# MCU2.net
KiCad netlist of a schematic drawn in Altium Designer
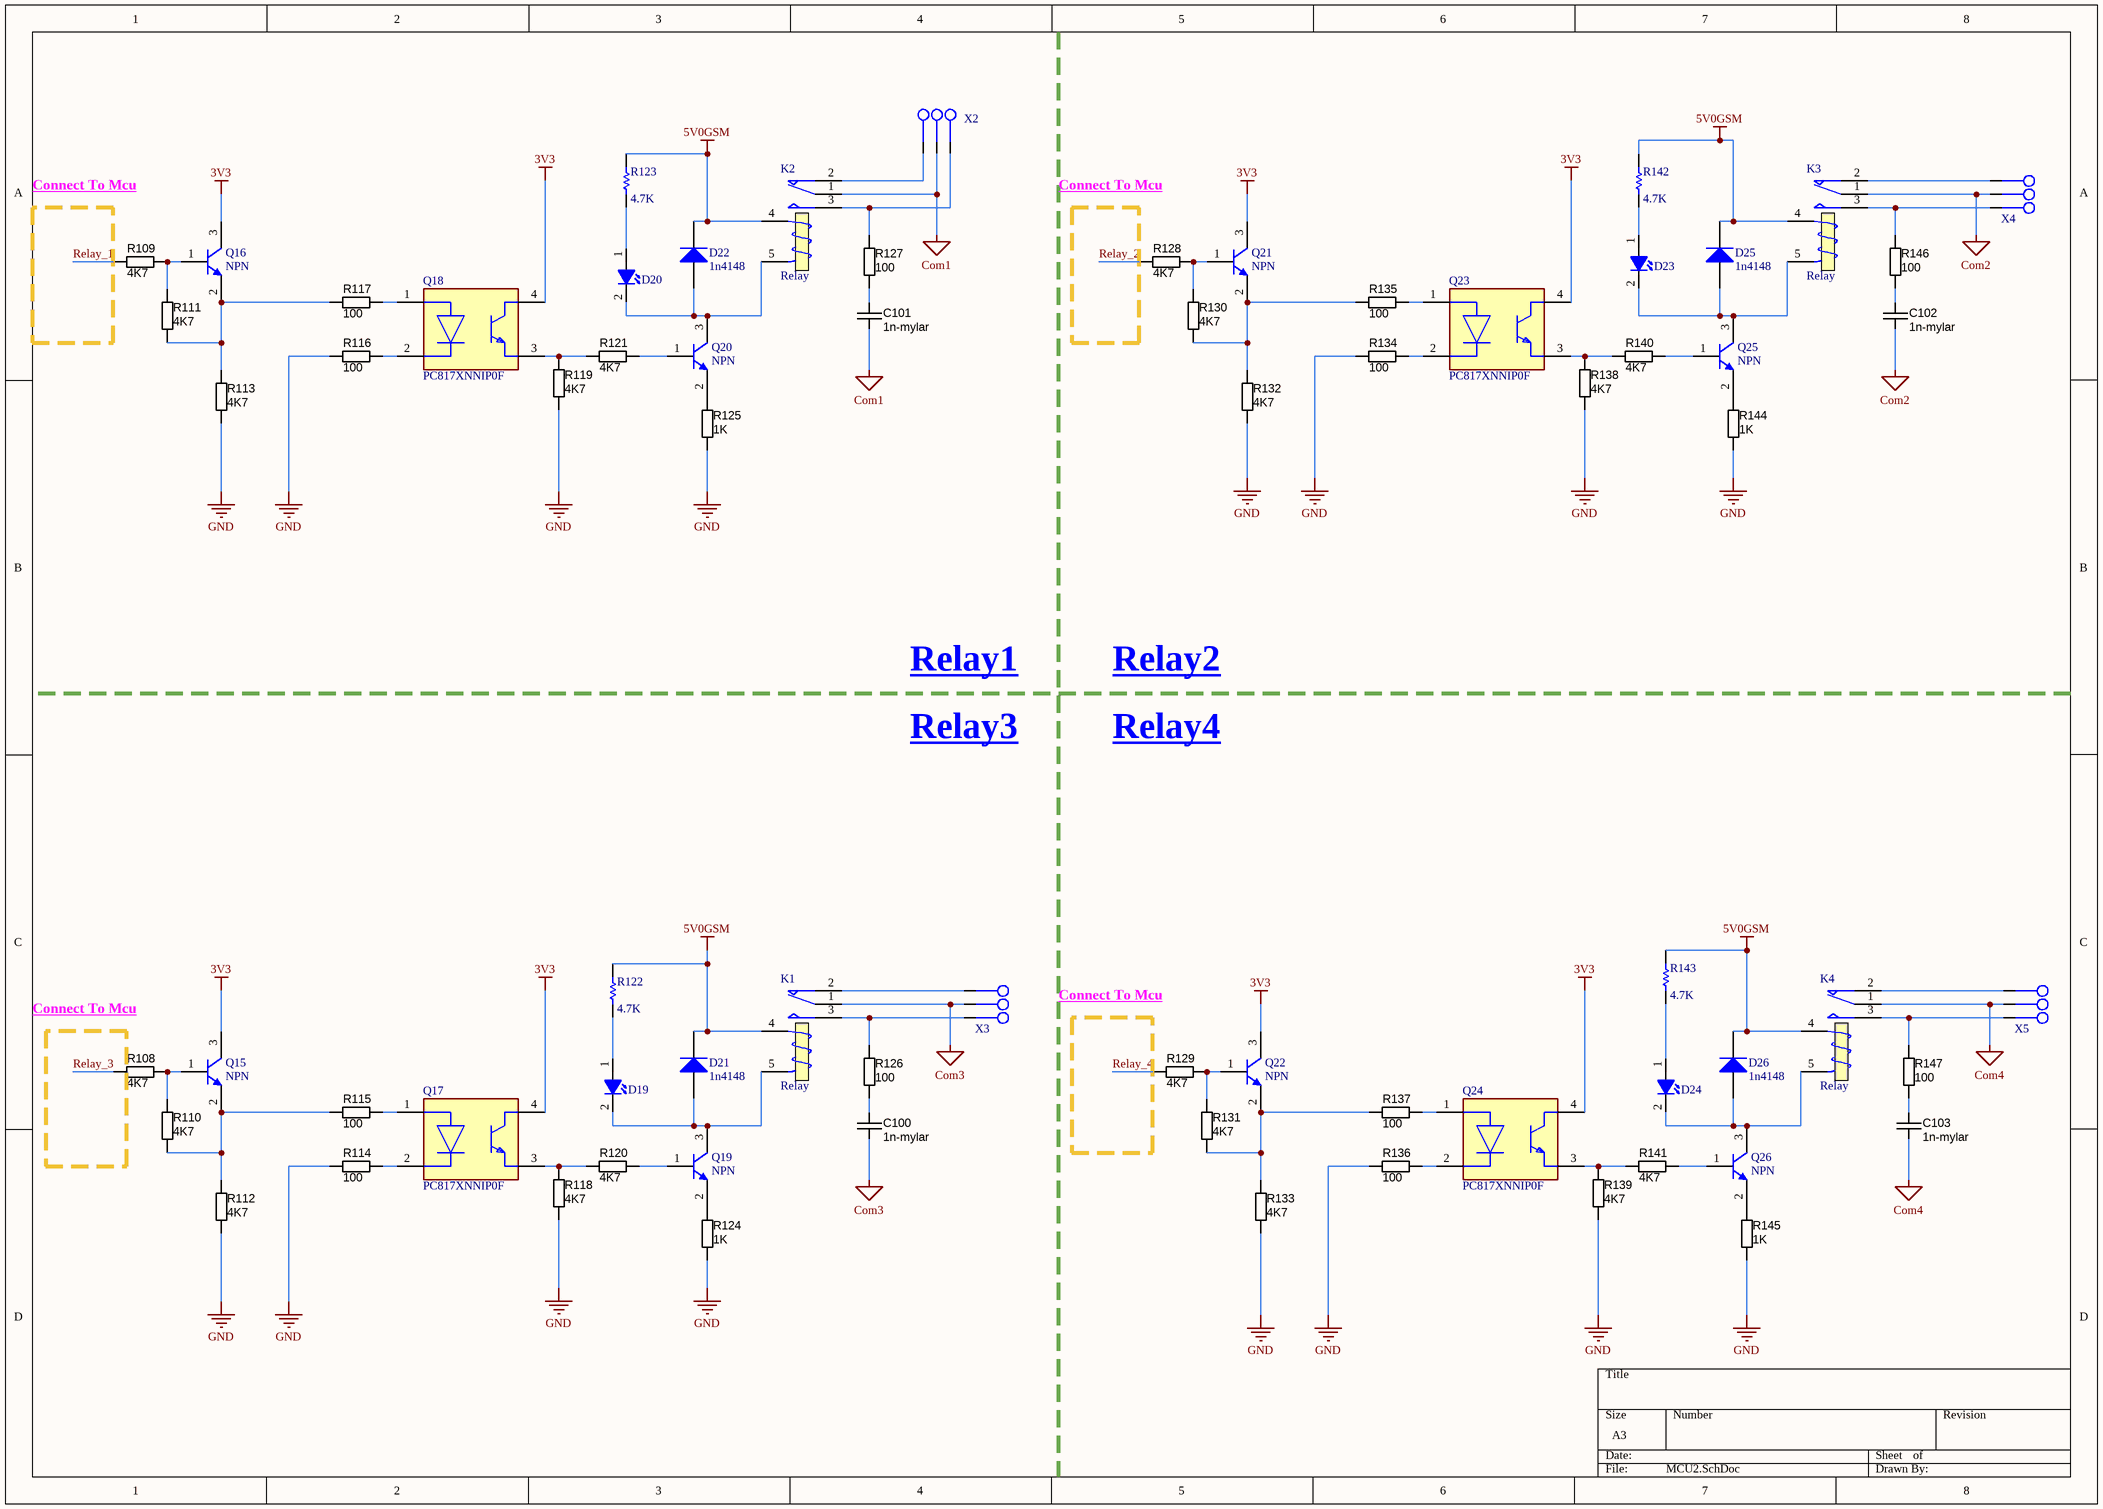
[diagram p0: MCU2.SchDoc]

(export (version "E")
  (design (tool "Eeschema 10.0.6"))
  (components
    (comp (ref "C100")
      (value "1n-mylar")
      (footprint "C_PLY_13X5")
      (description "Capacitor SMD Cer 1nF 10% 50V X7R 0603")
      (fields (field (name "TOLERANCE") "±10%") (field (name "Comment") "approved sub OK"))
      (libsource (lib "PBL - Capacitors") (part "CAPC_100n_0603_X7R_50V_10%"))
    )
    (comp (ref "C101")
      (value "1n-mylar")
      (footprint "C_PLY_13X5")
      (description "Capacitor SMD Cer 1nF 10% 50V X7R 0603")
      (fields (field (name "TOLERANCE") "±10%") (field (name "Comment") "approved sub OK"))
      (libsource (lib "PBL - Capacitors") (part "CAPC_100n_0603_X7R_50V_10%"))
    )
    (comp (ref "C102")
      (value "1n-mylar")
      (footprint "C_PLY_13X5")
      (description "Capacitor SMD Cer 1nF 10% 50V X7R 0603")
      (fields (field (name "TOLERANCE") "±10%") (field (name "Comment") "approved sub OK"))
      (libsource (lib "PBL - Capacitors") (part "CAPC_100n_0603_X7R_50V_10%"))
    )
    (comp (ref "C103")
      (value "1n-mylar")
      (footprint "C_PLY_13X5")
      (description "Capacitor SMD Cer 1nF 10% 50V X7R 0603")
      (fields (field (name "TOLERANCE") "±10%") (field (name "Comment") "approved sub OK"))
      (libsource (lib "PBL - Capacitors") (part "CAPC_100n_0603_X7R_50V_10%"))
    )
    (comp (ref "D19")
      (value "LED THD 5mm")
      (footprint "LED5MM_RED")
      (libsource (lib "LED") (part "LED THD 5mm"))
    )
    (comp (ref "D20")
      (value "LED THD 5mm")
      (footprint "LED5MM_RED")
      (libsource (lib "LED") (part "LED THD 5mm"))
    )
    (comp (ref "D21")
      (value "1n4148")
      (footprint "d_sod80")
      (description "Default Diode")
      (fields (field (name "PUBLISHER") "Altium Limited"))
      (libsource (lib "Miscellaneous Devices") (part "Diode"))
    )
    (comp (ref "D22")
      (value "1n4148")
      (footprint "d_sod80")
      (description "Default Diode")
      (fields (field (name "PUBLISHER") "Altium Limited"))
      (libsource (lib "Miscellaneous Devices") (part "Diode"))
    )
    (comp (ref "D23")
      (value "LED THD 5mm")
      (footprint "LED5MM_RED")
      (libsource (lib "LED") (part "LED THD 5mm"))
    )
    (comp (ref "D24")
      (value "LED THD 5mm")
      (footprint "LED5MM_RED")
      (libsource (lib "LED") (part "LED THD 5mm"))
    )
    (comp (ref "D25")
      (value "1n4148")
      (footprint "d_sod80")
      (description "Default Diode")
      (fields (field (name "PUBLISHER") "Altium Limited"))
      (libsource (lib "Miscellaneous Devices") (part "Diode"))
    )
    (comp (ref "D26")
      (value "1n4148")
      (footprint "d_sod80")
      (description "Default Diode")
      (fields (field (name "PUBLISHER") "Altium Limited"))
      (libsource (lib "Miscellaneous Devices") (part "Diode"))
    )
    (comp (ref "K1")
      (value "Relay")
      (footprint "REL_SPDT_5_2216")
      (description "SPDT Relay")
      (fields (field (name "PUBLISHER") "Altium Limited"))
      (libsource (lib "Miscellaneous Devices") (part "Relay"))
    )
    (comp (ref "K2")
      (value "Relay")
      (footprint "REL_SPDT_5_2216")
      (description "SPDT Relay")
      (fields (field (name "PUBLISHER") "Altium Limited"))
      (libsource (lib "Miscellaneous Devices") (part "Relay"))
    )
    (comp (ref "K3")
      (value "Relay")
      (footprint "REL_SPDT_5_2216")
      (description "SPDT Relay")
      (fields (field (name "PUBLISHER") "Altium Limited"))
      (libsource (lib "Miscellaneous Devices") (part "Relay"))
    )
    (comp (ref "K4")
      (value "Relay")
      (footprint "REL_SPDT_5_2216")
      (description "SPDT Relay")
      (fields (field (name "PUBLISHER") "Altium Limited"))
      (libsource (lib "Miscellaneous Devices") (part "Relay"))
    )
    (comp (ref "Q15")
      (value "NPN")
      (footprint "SOT23-3")
      (description "NPN Bipolar Transistor")
      (fields (field (name "PUBLISHER") "Altium Limited"))
      (libsource (lib "Miscellaneous Devices") (part "NPN"))
    )
    (comp (ref "Q16")
      (value "NPN")
      (footprint "SOT23-3")
      (description "NPN Bipolar Transistor")
      (fields (field (name "PUBLISHER") "Altium Limited"))
      (libsource (lib "Miscellaneous Devices") (part "NPN"))
    )
    (comp (ref "Q17")
      (value "PC817XNNIP0F")
      (footprint "FP-PC817XNNIP0F-MFG")
      (description "OPTOISOLATOR 5KV TRANS 4SMD")
      (libsource (lib "Altium Content Vault") (part "6470904bf6395c62928ee73e60120b8"))
    )
    (comp (ref "Q18")
      (value "PC817XNNIP0F")
      (footprint "FP-PC817XNNIP0F-MFG")
      (description "OPTOISOLATOR 5KV TRANS 4SMD")
      (libsource (lib "Altium Content Vault") (part "6470904bf6395c62928ee73e60120b8"))
    )
    (comp (ref "Q19")
      (value "NPN")
      (footprint "SOT23-3")
      (description "NPN Bipolar Transistor")
      (fields (field (name "PUBLISHER") "Altium Limited"))
      (libsource (lib "Miscellaneous Devices") (part "NPN"))
    )
    (comp (ref "Q20")
      (value "NPN")
      (footprint "SOT23-3")
      (description "NPN Bipolar Transistor")
      (fields (field (name "PUBLISHER") "Altium Limited"))
      (libsource (lib "Miscellaneous Devices") (part "NPN"))
    )
    (comp (ref "Q21")
      (value "NPN")
      (footprint "SOT23-3")
      (description "NPN Bipolar Transistor")
      (fields (field (name "PUBLISHER") "Altium Limited"))
      (libsource (lib "Miscellaneous Devices") (part "NPN"))
    )
    (comp (ref "Q22")
      (value "NPN")
      (footprint "SOT23-3")
      (description "NPN Bipolar Transistor")
      (fields (field (name "PUBLISHER") "Altium Limited"))
      (libsource (lib "Miscellaneous Devices") (part "NPN"))
    )
    (comp (ref "Q23")
      (value "PC817XNNIP0F")
      (footprint "FP-PC817XNNIP0F-MFG")
      (description "OPTOISOLATOR 5KV TRANS 4SMD")
      (libsource (lib "Altium Content Vault") (part "6470904bf6395c62928ee73e60120b8"))
    )
    (comp (ref "Q24")
      (value "PC817XNNIP0F")
      (footprint "FP-PC817XNNIP0F-MFG")
      (description "OPTOISOLATOR 5KV TRANS 4SMD")
      (libsource (lib "Altium Content Vault") (part "6470904bf6395c62928ee73e60120b8"))
    )
    (comp (ref "Q25")
      (value "NPN")
      (footprint "SOT23-3")
      (description "NPN Bipolar Transistor")
      (fields (field (name "PUBLISHER") "Altium Limited"))
      (libsource (lib "Miscellaneous Devices") (part "NPN"))
    )
    (comp (ref "Q26")
      (value "NPN")
      (footprint "SOT23-3")
      (description "NPN Bipolar Transistor")
      (fields (field (name "PUBLISHER") "Altium Limited"))
      (libsource (lib "Miscellaneous Devices") (part "NPN"))
    )
    (comp (ref "R108")
      (value "4K7")
      (footprint "RESC1608X55N")
      (description "Resistor SMD chip 4.7k Ohm 0.1W 5% 0603")
      (fields (field (name "TOLERANCE") "±5%") (field (name "Comment") "Thick Film"))
      (libsource (lib "") (part "RES_4K7_0603_5%_1"))
    )
    (comp (ref "R109")
      (value "4K7")
      (footprint "RESC1608X55N")
      (description "Resistor SMD chip 4.7k Ohm 0.1W 5% 0603")
      (fields (field (name "TOLERANCE") "±5%") (field (name "Comment") "Thick Film"))
      (libsource (lib "") (part "RES_4K7_0603_5%_1"))
    )
    (comp (ref "R110")
      (value "4K7")
      (footprint "RESC1608X55N")
      (description "Resistor SMD chip 4.7k Ohm 0.1W 5% 0603")
      (fields (field (name "TOLERANCE") "±5%") (field (name "Comment") "Thick Film"))
      (libsource (lib "PBL - Resistors") (part "RES_4K7_0603_5%"))
    )
    (comp (ref "R111")
      (value "4K7")
      (footprint "RESC1608X55N")
      (description "Resistor SMD chip 4.7k Ohm 0.1W 5% 0603")
      (fields (field (name "TOLERANCE") "±5%") (field (name "Comment") "Thick Film"))
      (libsource (lib "PBL - Resistors") (part "RES_4K7_0603_5%"))
    )
    (comp (ref "R112")
      (value "4K7")
      (footprint "RESC1608X55N")
      (description "Resistor SMD chip 4.7k Ohm 0.1W 5% 0603")
      (fields (field (name "TOLERANCE") "±5%") (field (name "Comment") "Thick Film"))
      (libsource (lib "PBL - Resistors") (part "RES_4K7_0603_5%"))
    )
    (comp (ref "R113")
      (value "4K7")
      (footprint "RESC1608X55N")
      (description "Resistor SMD chip 4.7k Ohm 0.1W 5% 0603")
      (fields (field (name "TOLERANCE") "±5%") (field (name "Comment") "Thick Film"))
      (libsource (lib "PBL - Resistors") (part "RES_4K7_0603_5%"))
    )
    (comp (ref "R114")
      (value "100")
      (footprint "RESC1608X55N")
      (description "Resistor SMD chip 100 Ohm 0.1W 5% 0603")
      (fields (field (name "TOLERANCE") "±5%") (field (name "Comment") "Thick Film"))
      (libsource (lib "") (part "RES_4K7_0603_5%_1"))
    )
    (comp (ref "R115")
      (value "100")
      (footprint "RESC1608X55N")
      (description "Resistor SMD chip 100 Ohm 0.1W 5% 0603")
      (fields (field (name "TOLERANCE") "±5%") (field (name "Comment") "Thick Film"))
      (libsource (lib "") (part "RES_4K7_0603_5%_1"))
    )
    (comp (ref "R116")
      (value "100")
      (footprint "RESC1608X55N")
      (description "Resistor SMD chip 100 Ohm 0.1W 5% 0603")
      (fields (field (name "TOLERANCE") "±5%") (field (name "Comment") "Thick Film"))
      (libsource (lib "") (part "RES_4K7_0603_5%_1"))
    )
    (comp (ref "R117")
      (value "100")
      (footprint "RESC1608X55N")
      (description "Resistor SMD chip 100 Ohm 0.1W 5% 0603")
      (fields (field (name "TOLERANCE") "±5%") (field (name "Comment") "Thick Film"))
      (libsource (lib "") (part "RES_4K7_0603_5%_1"))
    )
    (comp (ref "R118")
      (value "4K7")
      (footprint "RESC1608X55N")
      (description "Resistor SMD chip 4.7k Ohm 0.1W 5% 0603")
      (fields (field (name "TOLERANCE") "±5%") (field (name "Comment") "Thick Film"))
      (libsource (lib "PBL - Resistors") (part "RES_4K7_0603_5%"))
    )
    (comp (ref "R119")
      (value "4K7")
      (footprint "RESC1608X55N")
      (description "Resistor SMD chip 4.7k Ohm 0.1W 5% 0603")
      (fields (field (name "TOLERANCE") "±5%") (field (name "Comment") "Thick Film"))
      (libsource (lib "PBL - Resistors") (part "RES_4K7_0603_5%"))
    )
    (comp (ref "R120")
      (value "4K7")
      (footprint "RESC1608X55N")
      (description "Resistor SMD chip 4.7k Ohm 0.1W 5% 0603")
      (fields (field (name "TOLERANCE") "±5%") (field (name "Comment") "Thick Film"))
      (libsource (lib "") (part "RES_4K7_0603_5%_1"))
    )
    (comp (ref "R121")
      (value "4K7")
      (footprint "RESC1608X55N")
      (description "Resistor SMD chip 4.7k Ohm 0.1W 5% 0603")
      (fields (field (name "TOLERANCE") "±5%") (field (name "Comment") "Thick Film"))
      (libsource (lib "") (part "RES_4K7_0603_5%_1"))
    )
    (comp (ref "R122")
      (value "4.7K")
      (footprint "0603")
      (description "Resistor")
      (fields (field (name "Comment") "Res1") (field (name "PUBLISHER") "Altium Limited"))
      (libsource (lib "Miscellaneous Devices") (part "Res1"))
    )
    (comp (ref "R123")
      (value "4.7K")
      (footprint "0603")
      (description "Resistor")
      (fields (field (name "Comment") "Res1") (field (name "PUBLISHER") "Altium Limited"))
      (libsource (lib "Miscellaneous Devices") (part "Res1"))
    )
    (comp (ref "R124")
      (value "1K")
      (footprint "RESC1608X55N")
      (description "Resistor SMD chip 4.7k Ohm 0.1W 5% 0603")
      (fields (field (name "TOLERANCE") "±5%") (field (name "Comment") "Thick Film"))
      (libsource (lib "") (part "RES_4K7_0603_5%_2"))
    )
    (comp (ref "R125")
      (value "1K")
      (footprint "RESC1608X55N")
      (description "Resistor SMD chip 4.7k Ohm 0.1W 5% 0603")
      (fields (field (name "TOLERANCE") "±5%") (field (name "Comment") "Thick Film"))
      (libsource (lib "") (part "RES_4K7_0603_5%_2"))
    )
    (comp (ref "R126")
      (value "100")
      (footprint "R2512")
      (description "Resistor SMD chip 4.7k Ohm 0.1W 5% 0603")
      (fields (field (name "TOLERANCE") "±5%") (field (name "Comment") "Thick Film"))
      (libsource (lib "PBL - Resistors") (part "RES_4K7_0603_5%"))
    )
    (comp (ref "R127")
      (value "100")
      (footprint "R2512")
      (description "Resistor SMD chip 4.7k Ohm 0.1W 5% 0603")
      (fields (field (name "TOLERANCE") "±5%") (field (name "Comment") "Thick Film"))
      (libsource (lib "PBL - Resistors") (part "RES_4K7_0603_5%"))
    )
    (comp (ref "R128")
      (value "4K7")
      (footprint "RESC1608X55N")
      (description "Resistor SMD chip 4.7k Ohm 0.1W 5% 0603")
      (fields (field (name "TOLERANCE") "±5%") (field (name "Comment") "Thick Film"))
      (libsource (lib "") (part "RES_4K7_0603_5%_1"))
    )
    (comp (ref "R129")
      (value "4K7")
      (footprint "RESC1608X55N")
      (description "Resistor SMD chip 4.7k Ohm 0.1W 5% 0603")
      (fields (field (name "TOLERANCE") "±5%") (field (name "Comment") "Thick Film"))
      (libsource (lib "") (part "RES_4K7_0603_5%_1"))
    )
    (comp (ref "R130")
      (value "4K7")
      (footprint "RESC1608X55N")
      (description "Resistor SMD chip 4.7k Ohm 0.1W 5% 0603")
      (fields (field (name "TOLERANCE") "±5%") (field (name "Comment") "Thick Film"))
      (libsource (lib "PBL - Resistors") (part "RES_4K7_0603_5%"))
    )
    (comp (ref "R131")
      (value "4K7")
      (footprint "RESC1608X55N")
      (description "Resistor SMD chip 4.7k Ohm 0.1W 5% 0603")
      (fields (field (name "TOLERANCE") "±5%") (field (name "Comment") "Thick Film"))
      (libsource (lib "PBL - Resistors") (part "RES_4K7_0603_5%"))
    )
    (comp (ref "R132")
      (value "4K7")
      (footprint "RESC1608X55N")
      (description "Resistor SMD chip 4.7k Ohm 0.1W 5% 0603")
      (fields (field (name "TOLERANCE") "±5%") (field (name "Comment") "Thick Film"))
      (libsource (lib "PBL - Resistors") (part "RES_4K7_0603_5%"))
    )
    (comp (ref "R133")
      (value "4K7")
      (footprint "RESC1608X55N")
      (description "Resistor SMD chip 4.7k Ohm 0.1W 5% 0603")
      (fields (field (name "TOLERANCE") "±5%") (field (name "Comment") "Thick Film"))
      (libsource (lib "PBL - Resistors") (part "RES_4K7_0603_5%"))
    )
    (comp (ref "R134")
      (value "100")
      (footprint "RESC1608X55N")
      (description "Resistor SMD chip 100 Ohm 0.1W 5% 0603")
      (fields (field (name "TOLERANCE") "±5%") (field (name "Comment") "Thick Film"))
      (libsource (lib "") (part "RES_4K7_0603_5%_1"))
    )
    (comp (ref "R135")
      (value "100")
      (footprint "RESC1608X55N")
      (description "Resistor SMD chip 100 Ohm 0.1W 5% 0603")
      (fields (field (name "TOLERANCE") "±5%") (field (name "Comment") "Thick Film"))
      (libsource (lib "") (part "RES_4K7_0603_5%_1"))
    )
    (comp (ref "R136")
      (value "100")
      (footprint "RESC1608X55N")
      (description "Resistor SMD chip 100 Ohm 0.1W 5% 0603")
      (fields (field (name "TOLERANCE") "±5%") (field (name "Comment") "Thick Film"))
      (libsource (lib "") (part "RES_4K7_0603_5%_1"))
    )
    (comp (ref "R137")
      (value "100")
      (footprint "RESC1608X55N")
      (description "Resistor SMD chip 100 Ohm 0.1W 5% 0603")
      (fields (field (name "TOLERANCE") "±5%") (field (name "Comment") "Thick Film"))
      (libsource (lib "") (part "RES_4K7_0603_5%_1"))
    )
    (comp (ref "R138")
      (value "4K7")
      (footprint "RESC1608X55N")
      (description "Resistor SMD chip 4.7k Ohm 0.1W 5% 0603")
      (fields (field (name "TOLERANCE") "±5%") (field (name "Comment") "Thick Film"))
      (libsource (lib "PBL - Resistors") (part "RES_4K7_0603_5%"))
    )
    (comp (ref "R139")
      (value "4K7")
      (footprint "RESC1608X55N")
      (description "Resistor SMD chip 4.7k Ohm 0.1W 5% 0603")
      (fields (field (name "TOLERANCE") "±5%") (field (name "Comment") "Thick Film"))
      (libsource (lib "PBL - Resistors") (part "RES_4K7_0603_5%"))
    )
    (comp (ref "R140")
      (value "4K7")
      (footprint "RESC1608X55N")
      (description "Resistor SMD chip 4.7k Ohm 0.1W 5% 0603")
      (fields (field (name "TOLERANCE") "±5%") (field (name "Comment") "Thick Film"))
      (libsource (lib "") (part "RES_4K7_0603_5%_1"))
    )
    (comp (ref "R141")
      (value "4K7")
      (footprint "RESC1608X55N")
      (description "Resistor SMD chip 4.7k Ohm 0.1W 5% 0603")
      (fields (field (name "TOLERANCE") "±5%") (field (name "Comment") "Thick Film"))
      (libsource (lib "") (part "RES_4K7_0603_5%_1"))
    )
    (comp (ref "R142")
      (value "4.7K")
      (footprint "0603")
      (description "Resistor")
      (fields (field (name "Comment") "Res1") (field (name "PUBLISHER") "Altium Limited"))
      (libsource (lib "Miscellaneous Devices") (part "Res1"))
    )
    (comp (ref "R143")
      (value "4.7K")
      (footprint "0603")
      (description "Resistor")
      (fields (field (name "Comment") "Res1") (field (name "PUBLISHER") "Altium Limited"))
      (libsource (lib "Miscellaneous Devices") (part "Res1"))
    )
    (comp (ref "R144")
      (value "1K")
      (footprint "RESC1608X55N")
      (description "Resistor SMD chip 4.7k Ohm 0.1W 5% 0603")
      (fields (field (name "TOLERANCE") "±5%") (field (name "Comment") "Thick Film"))
      (libsource (lib "") (part "RES_4K7_0603_5%_2"))
    )
    (comp (ref "R145")
      (value "1K")
      (footprint "RESC1608X55N")
      (description "Resistor SMD chip 4.7k Ohm 0.1W 5% 0603")
      (fields (field (name "TOLERANCE") "±5%") (field (name "Comment") "Thick Film"))
      (libsource (lib "") (part "RES_4K7_0603_5%_2"))
    )
    (comp (ref "R146")
      (value "100")
      (footprint "R2512")
      (description "Resistor SMD chip 4.7k Ohm 0.1W 5% 0603")
      (fields (field (name "TOLERANCE") "±5%") (field (name "Comment") "Thick Film"))
      (libsource (lib "PBL - Resistors") (part "RES_4K7_0603_5%"))
    )
    (comp (ref "R147")
      (value "100")
      (footprint "R2512")
      (description "Resistor SMD chip 4.7k Ohm 0.1W 5% 0603")
      (fields (field (name "TOLERANCE") "±5%") (field (name "Comment") "Thick Film"))
      (libsource (lib "PBL - Resistors") (part "RES_4K7_0603_5%"))
    )
    (comp (ref "X2")
      (value "Phoenix MKDSN 03")
      (footprint "CON_MSTBA03")
      (libsource (lib "Connector") (part "Phoenix MKDSN 03"))
    )
    (comp (ref "X3")
      (value "Phoenix MKDSN 03")
      (footprint "CON_MSTBA03")
      (libsource (lib "Connector") (part "Phoenix MKDSN 03"))
    )
    (comp (ref "X4")
      (value "Phoenix MKDSN 03")
      (footprint "CON_MSTBA03")
      (libsource (lib "Connector") (part "Phoenix MKDSN 03"))
    )
    (comp (ref "X5")
      (value "Phoenix MKDSN 03")
      (footprint "CON_MSTBA03")
      (libsource (lib "Connector") (part "Phoenix MKDSN 03"))
    )
  )
  (nets
    (net (code "1") (name "/Relay_1") (class "Default")
      (node (ref "R109") (pin "1") (pinfunction "1_1") (pintype "passive"))
    )
    (net (code "2") (name "/Relay_2") (class "Default")
      (node (ref "R128") (pin "1") (pinfunction "1_1") (pintype "passive"))
    )
    (net (code "3") (name "/Relay_3") (class "Default")
      (node (ref "R108") (pin "1") (pinfunction "1_1") (pintype "passive"))
    )
    (net (code "4") (name "/Relay_4") (class "Default")
      (node (ref "R129") (pin "1") (pinfunction "1_1") (pintype "passive"))
    )
    (net (code "5") (name "3V3") (class "Default")
      (node (ref "Q15") (pin "3") (pinfunction "C_3") (pintype "passive"))
      (node (ref "Q16") (pin "3") (pinfunction "C_3") (pintype "passive"))
      (node (ref "Q17") (pin "4") (pinfunction "C_4") (pintype "passive"))
      (node (ref "Q18") (pin "4") (pinfunction "C_4") (pintype "passive"))
      (node (ref "Q21") (pin "3") (pinfunction "C_3") (pintype "passive"))
      (node (ref "Q22") (pin "3") (pinfunction "C_3") (pintype "passive"))
      (node (ref "Q23") (pin "4") (pinfunction "C_4") (pintype "passive"))
      (node (ref "Q24") (pin "4") (pinfunction "C_4") (pintype "passive"))
    )
    (net (code "6") (name "5V0GSM") (class "Default")
      (node (ref "D21") (pin "2") (pinfunction "K_2") (pintype "passive"))
      (node (ref "D22") (pin "2") (pinfunction "K_2") (pintype "passive"))
      (node (ref "D25") (pin "2") (pinfunction "K_2") (pintype "passive"))
      (node (ref "D26") (pin "2") (pinfunction "K_2") (pintype "passive"))
      (node (ref "K1") (pin "4") (pinfunction "T1_4") (pintype "passive"))
      (node (ref "K2") (pin "4") (pinfunction "T1_4") (pintype "passive"))
      (node (ref "K3") (pin "4") (pinfunction "T1_4") (pintype "passive"))
      (node (ref "K4") (pin "4") (pinfunction "T1_4") (pintype "passive"))
      (node (ref "R122") (pin "2") (pinfunction "2_2") (pintype "passive"))
      (node (ref "R123") (pin "2") (pinfunction "2_2") (pintype "passive"))
      (node (ref "R142") (pin "2") (pinfunction "2_2") (pintype "passive"))
      (node (ref "R143") (pin "2") (pinfunction "2_2") (pintype "passive"))
    )
    (net (code "7") (name "Com1") (class "Default")
      (node (ref "C101") (pin "2") (pintype "passive"))
      (node (ref "K2") (pin "1") (pinfunction "COM_1") (pintype "passive"))
      (node (ref "X2") (pin "2") (pinfunction "2_2") (pintype "passive"))
    )
    (net (code "8") (name "Com2") (class "Default")
      (node (ref "C102") (pin "2") (pintype "passive"))
      (node (ref "K3") (pin "1") (pinfunction "COM_1") (pintype "passive"))
      (node (ref "X4") (pin "2") (pinfunction "2_2") (pintype "passive"))
    )
    (net (code "9") (name "Com3") (class "Default")
      (node (ref "C100") (pin "2") (pintype "passive"))
      (node (ref "K1") (pin "1") (pinfunction "COM_1") (pintype "passive"))
      (node (ref "X3") (pin "2") (pinfunction "2_2") (pintype "passive"))
    )
    (net (code "10") (name "Com4") (class "Default")
      (node (ref "C103") (pin "2") (pintype "passive"))
      (node (ref "K4") (pin "1") (pinfunction "COM_1") (pintype "passive"))
      (node (ref "X5") (pin "2") (pinfunction "2_2") (pintype "passive"))
    )
    (net (code "11") (name "GND") (class "Default")
      (node (ref "R112") (pin "1") (pinfunction "1_1") (pintype "passive"))
      (node (ref "R113") (pin "1") (pinfunction "1_1") (pintype "passive"))
      (node (ref "R114") (pin "1") (pinfunction "1_1") (pintype "passive"))
      (node (ref "R116") (pin "1") (pinfunction "1_1") (pintype "passive"))
      (node (ref "R118") (pin "1") (pinfunction "1_1") (pintype "passive"))
      (node (ref "R119") (pin "1") (pinfunction "1_1") (pintype "passive"))
      (node (ref "R124") (pin "2") (pinfunction "2_2") (pintype "passive"))
      (node (ref "R125") (pin "2") (pinfunction "2_2") (pintype "passive"))
      (node (ref "R132") (pin "1") (pinfunction "1_1") (pintype "passive"))
      (node (ref "R133") (pin "1") (pinfunction "1_1") (pintype "passive"))
      (node (ref "R134") (pin "1") (pinfunction "1_1") (pintype "passive"))
      (node (ref "R136") (pin "1") (pinfunction "1_1") (pintype "passive"))
      (node (ref "R138") (pin "1") (pinfunction "1_1") (pintype "passive"))
      (node (ref "R139") (pin "1") (pinfunction "1_1") (pintype "passive"))
      (node (ref "R144") (pin "2") (pinfunction "2_2") (pintype "passive"))
      (node (ref "R145") (pin "2") (pinfunction "2_2") (pintype "passive"))
    )
    (net (code "12") (name "Net-(C100-Pad1)") (class "Default")
      (node (ref "C100") (pin "1") (pintype "passive"))
      (node (ref "R126") (pin "1") (pinfunction "1_1") (pintype "passive"))
    )
    (net (code "13") (name "Net-(C101-Pad1)") (class "Default")
      (node (ref "C101") (pin "1") (pintype "passive"))
      (node (ref "R127") (pin "1") (pinfunction "1_1") (pintype "passive"))
    )
    (net (code "14") (name "Net-(C102-Pad1)") (class "Default")
      (node (ref "C102") (pin "1") (pintype "passive"))
      (node (ref "R146") (pin "1") (pinfunction "1_1") (pintype "passive"))
    )
    (net (code "15") (name "Net-(C103-Pad1)") (class "Default")
      (node (ref "C103") (pin "1") (pintype "passive"))
      (node (ref "R147") (pin "1") (pinfunction "1_1") (pintype "passive"))
    )
    (net (code "16") (name "Net-(D19-ANODE)") (class "Default")
      (node (ref "D19") (pin "1") (pinfunction "ANODE_1") (pintype "passive"))
      (node (ref "R122") (pin "1") (pinfunction "1_1") (pintype "passive"))
    )
    (net (code "17") (name "Net-(D19-CATHODE)") (class "Default")
      (node (ref "D19") (pin "2") (pinfunction "CATHODE_2") (pintype "passive"))
      (node (ref "D21") (pin "1") (pinfunction "A_1") (pintype "passive"))
      (node (ref "K1") (pin "5") (pinfunction "T2_5") (pintype "passive"))
      (node (ref "Q19") (pin "3") (pinfunction "C_3") (pintype "passive"))
    )
    (net (code "18") (name "Net-(D20-ANODE)") (class "Default")
      (node (ref "D20") (pin "1") (pinfunction "ANODE_1") (pintype "passive"))
      (node (ref "R123") (pin "1") (pinfunction "1_1") (pintype "passive"))
    )
    (net (code "19") (name "Net-(D20-CATHODE)") (class "Default")
      (node (ref "D20") (pin "2") (pinfunction "CATHODE_2") (pintype "passive"))
      (node (ref "D22") (pin "1") (pinfunction "A_1") (pintype "passive"))
      (node (ref "K2") (pin "5") (pinfunction "T2_5") (pintype "passive"))
      (node (ref "Q20") (pin "3") (pinfunction "C_3") (pintype "passive"))
    )
    (net (code "20") (name "Net-(D23-ANODE)") (class "Default")
      (node (ref "D23") (pin "1") (pinfunction "ANODE_1") (pintype "passive"))
      (node (ref "R142") (pin "1") (pinfunction "1_1") (pintype "passive"))
    )
    (net (code "21") (name "Net-(D23-CATHODE)") (class "Default")
      (node (ref "D23") (pin "2") (pinfunction "CATHODE_2") (pintype "passive"))
      (node (ref "D25") (pin "1") (pinfunction "A_1") (pintype "passive"))
      (node (ref "K3") (pin "5") (pinfunction "T2_5") (pintype "passive"))
      (node (ref "Q25") (pin "3") (pinfunction "C_3") (pintype "passive"))
    )
    (net (code "22") (name "Net-(D24-ANODE)") (class "Default")
      (node (ref "D24") (pin "1") (pinfunction "ANODE_1") (pintype "passive"))
      (node (ref "R143") (pin "1") (pinfunction "1_1") (pintype "passive"))
    )
    (net (code "23") (name "Net-(D24-CATHODE)") (class "Default")
      (node (ref "D24") (pin "2") (pinfunction "CATHODE_2") (pintype "passive"))
      (node (ref "D26") (pin "1") (pinfunction "A_1") (pintype "passive"))
      (node (ref "K4") (pin "5") (pinfunction "T2_5") (pintype "passive"))
      (node (ref "Q26") (pin "3") (pinfunction "C_3") (pintype "passive"))
    )
    (net (code "24") (name "Net-(K1-NC)") (class "Default")
      (node (ref "K1") (pin "2") (pinfunction "NC_2") (pintype "passive"))
      (node (ref "X3") (pin "3") (pinfunction "1_3") (pintype "passive"))
    )
    (net (code "25") (name "Net-(K1-NO)") (class "Default")
      (node (ref "K1") (pin "3") (pinfunction "NO_3") (pintype "passive"))
      (node (ref "R126") (pin "2") (pinfunction "2_2") (pintype "passive"))
      (node (ref "X3") (pin "1") (pinfunction "3_1") (pintype "passive"))
    )
    (net (code "26") (name "Net-(K2-NC)") (class "Default")
      (node (ref "K2") (pin "2") (pinfunction "NC_2") (pintype "passive"))
      (node (ref "X2") (pin "3") (pinfunction "1_3") (pintype "passive"))
    )
    (net (code "27") (name "Net-(K2-NO)") (class "Default")
      (node (ref "K2") (pin "3") (pinfunction "NO_3") (pintype "passive"))
      (node (ref "R127") (pin "2") (pinfunction "2_2") (pintype "passive"))
      (node (ref "X2") (pin "1") (pinfunction "3_1") (pintype "passive"))
    )
    (net (code "28") (name "Net-(K3-NC)") (class "Default")
      (node (ref "K3") (pin "2") (pinfunction "NC_2") (pintype "passive"))
      (node (ref "X4") (pin "3") (pinfunction "1_3") (pintype "passive"))
    )
    (net (code "29") (name "Net-(K3-NO)") (class "Default")
      (node (ref "K3") (pin "3") (pinfunction "NO_3") (pintype "passive"))
      (node (ref "R146") (pin "2") (pinfunction "2_2") (pintype "passive"))
      (node (ref "X4") (pin "1") (pinfunction "3_1") (pintype "passive"))
    )
    (net (code "30") (name "Net-(K4-NC)") (class "Default")
      (node (ref "K4") (pin "2") (pinfunction "NC_2") (pintype "passive"))
      (node (ref "X5") (pin "3") (pinfunction "1_3") (pintype "passive"))
    )
    (net (code "31") (name "Net-(K4-NO)") (class "Default")
      (node (ref "K4") (pin "3") (pinfunction "NO_3") (pintype "passive"))
      (node (ref "R147") (pin "2") (pinfunction "2_2") (pintype "passive"))
      (node (ref "X5") (pin "1") (pinfunction "3_1") (pintype "passive"))
    )
    (net (code "32") (name "Net-(Q15-B)") (class "Default")
      (node (ref "Q15") (pin "1") (pinfunction "B_1") (pintype "passive"))
      (node (ref "R108") (pin "2") (pinfunction "2_2") (pintype "passive"))
      (node (ref "R110") (pin "2") (pinfunction "2_2") (pintype "passive"))
    )
    (net (code "33") (name "Net-(Q15-E)") (class "Default")
      (node (ref "Q15") (pin "2") (pinfunction "E_2") (pintype "passive"))
      (node (ref "R110") (pin "1") (pinfunction "1_1") (pintype "passive"))
      (node (ref "R112") (pin "2") (pinfunction "2_2") (pintype "passive"))
      (node (ref "R115") (pin "1") (pinfunction "1_1") (pintype "passive"))
    )
    (net (code "34") (name "Net-(Q16-B)") (class "Default")
      (node (ref "Q16") (pin "1") (pinfunction "B_1") (pintype "passive"))
      (node (ref "R109") (pin "2") (pinfunction "2_2") (pintype "passive"))
      (node (ref "R111") (pin "2") (pinfunction "2_2") (pintype "passive"))
    )
    (net (code "35") (name "Net-(Q16-E)") (class "Default")
      (node (ref "Q16") (pin "2") (pinfunction "E_2") (pintype "passive"))
      (node (ref "R111") (pin "1") (pinfunction "1_1") (pintype "passive"))
      (node (ref "R113") (pin "2") (pinfunction "2_2") (pintype "passive"))
      (node (ref "R117") (pin "1") (pinfunction "1_1") (pintype "passive"))
    )
    (net (code "36") (name "Net-(Q17-A)") (class "Default")
      (node (ref "Q17") (pin "1") (pinfunction "A_1") (pintype "passive"))
      (node (ref "R115") (pin "2") (pinfunction "2_2") (pintype "passive"))
    )
    (net (code "37") (name "Net-(Q17-C-Pad2)") (class "Default")
      (node (ref "Q17") (pin "2") (pinfunction "C_2") (pintype "passive"))
      (node (ref "R114") (pin "2") (pinfunction "2_2") (pintype "passive"))
    )
    (net (code "38") (name "Net-(Q17-E)") (class "Default")
      (node (ref "Q17") (pin "3") (pinfunction "E_3") (pintype "passive"))
      (node (ref "R118") (pin "2") (pinfunction "2_2") (pintype "passive"))
      (node (ref "R120") (pin "1") (pinfunction "1_1") (pintype "passive"))
    )
    (net (code "39") (name "Net-(Q18-A)") (class "Default")
      (node (ref "Q18") (pin "1") (pinfunction "A_1") (pintype "passive"))
      (node (ref "R117") (pin "2") (pinfunction "2_2") (pintype "passive"))
    )
    (net (code "40") (name "Net-(Q18-C-Pad2)") (class "Default")
      (node (ref "Q18") (pin "2") (pinfunction "C_2") (pintype "passive"))
      (node (ref "R116") (pin "2") (pinfunction "2_2") (pintype "passive"))
    )
    (net (code "41") (name "Net-(Q18-E)") (class "Default")
      (node (ref "Q18") (pin "3") (pinfunction "E_3") (pintype "passive"))
      (node (ref "R119") (pin "2") (pinfunction "2_2") (pintype "passive"))
      (node (ref "R121") (pin "1") (pinfunction "1_1") (pintype "passive"))
    )
    (net (code "42") (name "Net-(Q19-B)") (class "Default")
      (node (ref "Q19") (pin "1") (pinfunction "B_1") (pintype "passive"))
      (node (ref "R120") (pin "2") (pinfunction "2_2") (pintype "passive"))
    )
    (net (code "43") (name "Net-(Q19-E)") (class "Default")
      (node (ref "Q19") (pin "2") (pinfunction "E_2") (pintype "passive"))
      (node (ref "R124") (pin "1") (pinfunction "1_1") (pintype "passive"))
    )
    (net (code "44") (name "Net-(Q20-B)") (class "Default")
      (node (ref "Q20") (pin "1") (pinfunction "B_1") (pintype "passive"))
      (node (ref "R121") (pin "2") (pinfunction "2_2") (pintype "passive"))
    )
    (net (code "45") (name "Net-(Q20-E)") (class "Default")
      (node (ref "Q20") (pin "2") (pinfunction "E_2") (pintype "passive"))
      (node (ref "R125") (pin "1") (pinfunction "1_1") (pintype "passive"))
    )
    (net (code "46") (name "Net-(Q21-B)") (class "Default")
      (node (ref "Q21") (pin "1") (pinfunction "B_1") (pintype "passive"))
      (node (ref "R128") (pin "2") (pinfunction "2_2") (pintype "passive"))
      (node (ref "R130") (pin "2") (pinfunction "2_2") (pintype "passive"))
    )
    (net (code "47") (name "Net-(Q21-E)") (class "Default")
      (node (ref "Q21") (pin "2") (pinfunction "E_2") (pintype "passive"))
      (node (ref "R130") (pin "1") (pinfunction "1_1") (pintype "passive"))
      (node (ref "R132") (pin "2") (pinfunction "2_2") (pintype "passive"))
      (node (ref "R135") (pin "1") (pinfunction "1_1") (pintype "passive"))
    )
    (net (code "48") (name "Net-(Q22-B)") (class "Default")
      (node (ref "Q22") (pin "1") (pinfunction "B_1") (pintype "passive"))
      (node (ref "R129") (pin "2") (pinfunction "2_2") (pintype "passive"))
      (node (ref "R131") (pin "2") (pinfunction "2_2") (pintype "passive"))
    )
    (net (code "49") (name "Net-(Q22-E)") (class "Default")
      (node (ref "Q22") (pin "2") (pinfunction "E_2") (pintype "passive"))
      (node (ref "R131") (pin "1") (pinfunction "1_1") (pintype "passive"))
      (node (ref "R133") (pin "2") (pinfunction "2_2") (pintype "passive"))
      (node (ref "R137") (pin "1") (pinfunction "1_1") (pintype "passive"))
    )
    (net (code "50") (name "Net-(Q23-A)") (class "Default")
      (node (ref "Q23") (pin "1") (pinfunction "A_1") (pintype "passive"))
      (node (ref "R135") (pin "2") (pinfunction "2_2") (pintype "passive"))
    )
    (net (code "51") (name "Net-(Q23-C-Pad2)") (class "Default")
      (node (ref "Q23") (pin "2") (pinfunction "C_2") (pintype "passive"))
      (node (ref "R134") (pin "2") (pinfunction "2_2") (pintype "passive"))
    )
    (net (code "52") (name "Net-(Q23-E)") (class "Default")
      (node (ref "Q23") (pin "3") (pinfunction "E_3") (pintype "passive"))
      (node (ref "R138") (pin "2") (pinfunction "2_2") (pintype "passive"))
      (node (ref "R140") (pin "1") (pinfunction "1_1") (pintype "passive"))
    )
    (net (code "53") (name "Net-(Q24-A)") (class "Default")
      (node (ref "Q24") (pin "1") (pinfunction "A_1") (pintype "passive"))
      (node (ref "R137") (pin "2") (pinfunction "2_2") (pintype "passive"))
    )
    (net (code "54") (name "Net-(Q24-C-Pad2)") (class "Default")
      (node (ref "Q24") (pin "2") (pinfunction "C_2") (pintype "passive"))
      (node (ref "R136") (pin "2") (pinfunction "2_2") (pintype "passive"))
    )
    (net (code "55") (name "Net-(Q24-E)") (class "Default")
      (node (ref "Q24") (pin "3") (pinfunction "E_3") (pintype "passive"))
      (node (ref "R139") (pin "2") (pinfunction "2_2") (pintype "passive"))
      (node (ref "R141") (pin "1") (pinfunction "1_1") (pintype "passive"))
    )
    (net (code "56") (name "Net-(Q25-B)") (class "Default")
      (node (ref "Q25") (pin "1") (pinfunction "B_1") (pintype "passive"))
      (node (ref "R140") (pin "2") (pinfunction "2_2") (pintype "passive"))
    )
    (net (code "57") (name "Net-(Q25-E)") (class "Default")
      (node (ref "Q25") (pin "2") (pinfunction "E_2") (pintype "passive"))
      (node (ref "R144") (pin "1") (pinfunction "1_1") (pintype "passive"))
    )
    (net (code "58") (name "Net-(Q26-B)") (class "Default")
      (node (ref "Q26") (pin "1") (pinfunction "B_1") (pintype "passive"))
      (node (ref "R141") (pin "2") (pinfunction "2_2") (pintype "passive"))
    )
    (net (code "59") (name "Net-(Q26-E)") (class "Default")
      (node (ref "Q26") (pin "2") (pinfunction "E_2") (pintype "passive"))
      (node (ref "R145") (pin "1") (pinfunction "1_1") (pintype "passive"))
    )
  )
)
